# Camera-Interface.net
KiCad netlist of a schematic drawn in Altium Designer
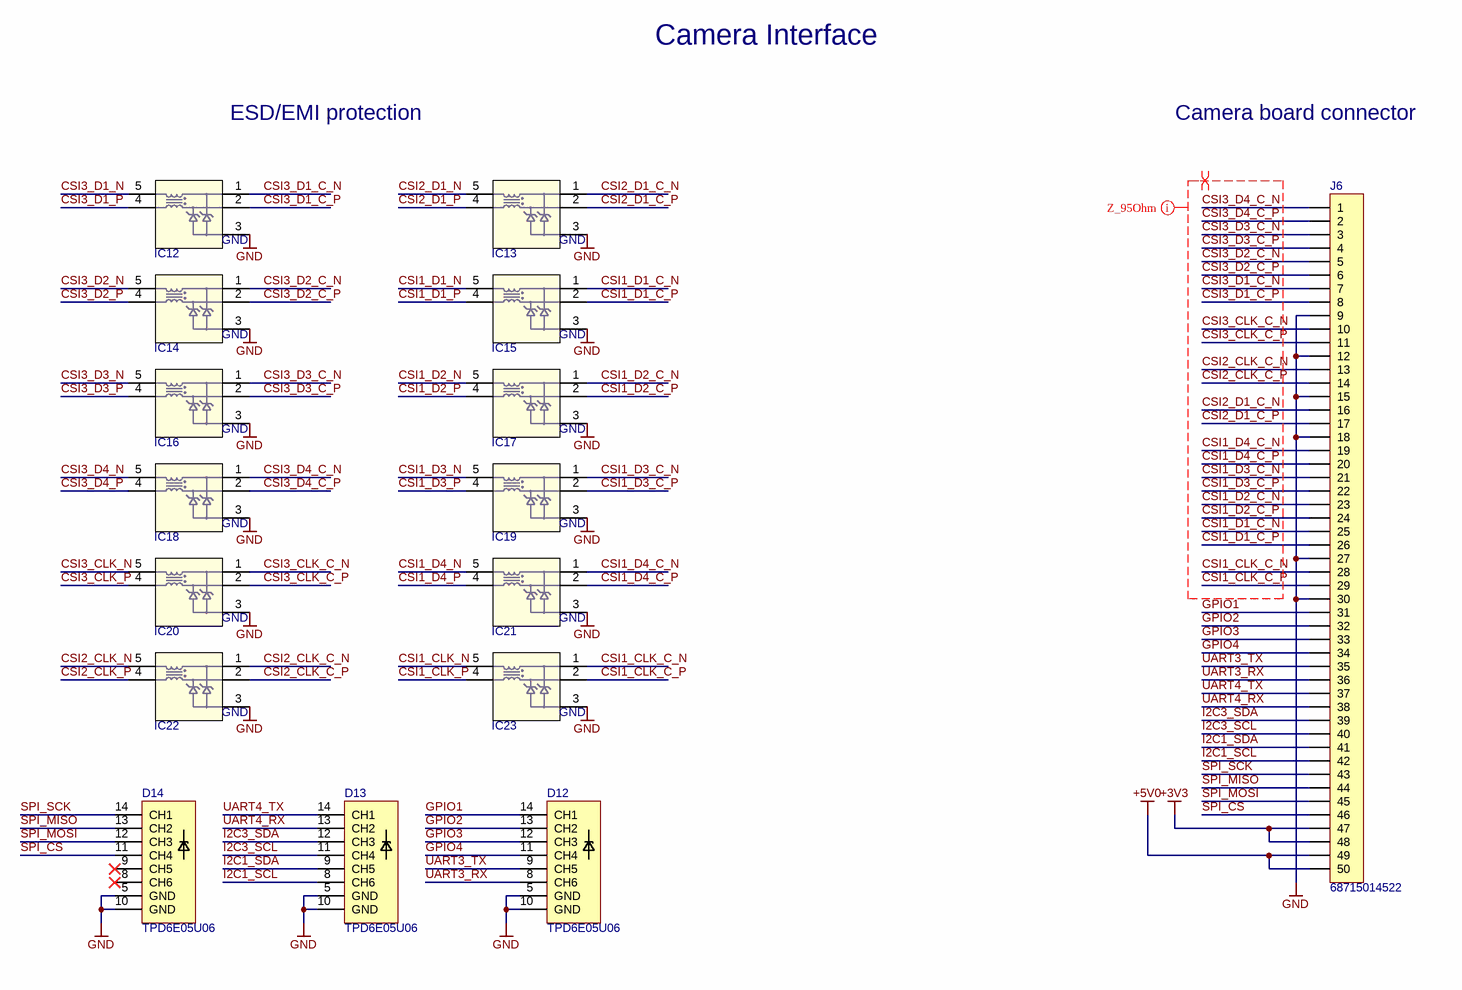
[diagram p0: Camera-Interface.SchDoc]

(export (version "E")
  (design (tool "Eeschema 10.0.6"))
  (components
    (comp (ref "D12")
      (value "TPD6E05U06")
      (footprint "TPD6E05U06_PASS")
      (description "ESD Suppressors 6-CH Pass through layout")
      (fields
        (field (name "PART NUMBER") "TPD6E05U06_PASS")
        (field (name "MANUFACTURER") "Texas Instruments")
      )
      (libsource (lib "TK1Baseboard") (part "TPD6E05U06_PASS"))
    )
    (comp (ref "D13")
      (value "TPD6E05U06")
      (footprint "TPD6E05U06_PASS")
      (description "ESD Suppressors 6-CH Pass through layout")
      (fields
        (field (name "PART NUMBER") "TPD6E05U06_PASS")
        (field (name "MANUFACTURER") "Texas Instruments")
      )
      (libsource (lib "TK1Baseboard") (part "TPD6E05U06_PASS"))
    )
    (comp (ref "D14")
      (value "TPD6E05U06")
      (footprint "TPD6E05U06_PASS")
      (description "ESD Suppressors 6-CH Pass through layout")
      (fields
        (field (name "PART NUMBER") "TPD6E05U06_PASS")
        (field (name "MANUFACTURER") "Texas Instruments")
      )
      (libsource (lib "TK1Baseboard") (part "TPD6E05U06_PASS"))
    )
    (comp (ref "IC12")
      (value "EClamp8052P")
      (footprint "SGP1917N5")
      (description "2-Line Common Mode Filter and Low Capacitance ESD Protection for MIPI USB")
      (fields (field (name "MANUFACTURER") "SEMTECH") (field (name "MPN") "ECLAMP8052P.TCT"))
      (libsource (lib "TK1Baseboard") (part "EClamp8052P"))
    )
    (comp (ref "IC13")
      (value "EClamp8052P")
      (footprint "SGP1917N5")
      (description "2-Line Common Mode Filter and Low Capacitance ESD Protection for MIPI USB")
      (fields (field (name "MANUFACTURER") "SEMTECH") (field (name "MPN") "ECLAMP8052P.TCT"))
      (libsource (lib "TK1Baseboard") (part "EClamp8052P"))
    )
    (comp (ref "IC14")
      (value "EClamp8052P")
      (footprint "SGP1917N5")
      (description "2-Line Common Mode Filter and Low Capacitance ESD Protection for MIPI USB")
      (fields (field (name "MANUFACTURER") "SEMTECH") (field (name "MPN") "ECLAMP8052P.TCT"))
      (libsource (lib "TK1Baseboard") (part "EClamp8052P"))
    )
    (comp (ref "IC15")
      (value "EClamp8052P")
      (footprint "SGP1917N5")
      (description "2-Line Common Mode Filter and Low Capacitance ESD Protection for MIPI USB")
      (fields (field (name "MANUFACTURER") "SEMTECH") (field (name "MPN") "ECLAMP8052P.TCT"))
      (libsource (lib "TK1Baseboard") (part "EClamp8052P"))
    )
    (comp (ref "IC16")
      (value "EClamp8052P")
      (footprint "SGP1917N5")
      (description "2-Line Common Mode Filter and Low Capacitance ESD Protection for MIPI USB")
      (fields (field (name "MANUFACTURER") "SEMTECH") (field (name "MPN") "ECLAMP8052P.TCT"))
      (libsource (lib "TK1Baseboard") (part "EClamp8052P"))
    )
    (comp (ref "IC17")
      (value "EClamp8052P")
      (footprint "SGP1917N5")
      (description "2-Line Common Mode Filter and Low Capacitance ESD Protection for MIPI USB")
      (fields (field (name "MANUFACTURER") "SEMTECH") (field (name "MPN") "ECLAMP8052P.TCT"))
      (libsource (lib "TK1Baseboard") (part "EClamp8052P"))
    )
    (comp (ref "IC18")
      (value "EClamp8052P")
      (footprint "SGP1917N5")
      (description "2-Line Common Mode Filter and Low Capacitance ESD Protection for MIPI USB")
      (fields (field (name "MANUFACTURER") "SEMTECH") (field (name "MPN") "ECLAMP8052P.TCT"))
      (libsource (lib "TK1Baseboard") (part "EClamp8052P"))
    )
    (comp (ref "IC19")
      (value "EClamp8052P")
      (footprint "SGP1917N5")
      (description "2-Line Common Mode Filter and Low Capacitance ESD Protection for MIPI USB")
      (fields (field (name "MANUFACTURER") "SEMTECH") (field (name "MPN") "ECLAMP8052P.TCT"))
      (libsource (lib "TK1Baseboard") (part "EClamp8052P"))
    )
    (comp (ref "IC20")
      (value "EClamp8052P")
      (footprint "SGP1917N5")
      (description "2-Line Common Mode Filter and Low Capacitance ESD Protection for MIPI USB")
      (fields (field (name "MANUFACTURER") "SEMTECH") (field (name "MPN") "ECLAMP8052P.TCT"))
      (libsource (lib "TK1Baseboard") (part "EClamp8052P"))
    )
    (comp (ref "IC21")
      (value "EClamp8052P")
      (footprint "SGP1917N5")
      (description "2-Line Common Mode Filter and Low Capacitance ESD Protection for MIPI USB")
      (fields (field (name "MANUFACTURER") "SEMTECH") (field (name "MPN") "ECLAMP8052P.TCT"))
      (libsource (lib "TK1Baseboard") (part "EClamp8052P"))
    )
    (comp (ref "IC22")
      (value "EClamp8052P")
      (footprint "SGP1917N5")
      (description "2-Line Common Mode Filter and Low Capacitance ESD Protection for MIPI USB")
      (fields (field (name "MANUFACTURER") "SEMTECH") (field (name "MPN") "ECLAMP8052P.TCT"))
      (libsource (lib "TK1Baseboard") (part "EClamp8052P"))
    )
    (comp (ref "IC23")
      (value "EClamp8052P")
      (footprint "SGP1917N5")
      (description "2-Line Common Mode Filter and Low Capacitance ESD Protection for MIPI USB")
      (fields (field (name "MANUFACTURER") "SEMTECH") (field (name "MPN") "ECLAMP8052P.TCT"))
      (libsource (lib "TK1Baseboard") (part "EClamp8052P"))
    )
    (comp (ref "J6")
      (value "68715014522")
      (footprint "68715014522")
      (description "0.50mm SMT ZIF Horizontal Bottom Contact WR-FPC")
      (fields
        (field (name "MANUFACTURER") "WURTH ELEKTRONIK")
        (field (name "PART NUMBER") "WE-687-150-145-22")
      )
      (libsource (lib "TK1Baseboard") (part "1X50"))
    )
  )
  (nets
    (net (code "1") (name "+3V3") (class "Default")
      (node (ref "J6") (pin "47") (pinfunction "47_47") (pintype "passive"))
      (node (ref "J6") (pin "48") (pinfunction "48_48") (pintype "passive"))
    )
    (net (code "2") (name "+5V0") (class "Default")
      (node (ref "J6") (pin "49") (pinfunction "49_49") (pintype "passive"))
      (node (ref "J6") (pin "50") (pinfunction "50_50") (pintype "passive"))
    )
    (net (code "3") (name "/CSI1_CLK_C_N") (class "Default")
      (node (ref "IC23") (pin "1") (pinfunction "1_1") (pintype "passive"))
      (node (ref "J6") (pin "28") (pinfunction "28_28") (pintype "passive"))
    )
    (net (code "4") (name "/CSI1_CLK_C_P") (class "Default")
      (node (ref "IC23") (pin "2") (pinfunction "2_2") (pintype "passive"))
      (node (ref "J6") (pin "29") (pinfunction "29_29") (pintype "passive"))
    )
    (net (code "5") (name "/CSI1_CLK_N") (class "Default")
      (node (ref "IC23") (pin "5") (pinfunction "5_5") (pintype "passive"))
    )
    (net (code "6") (name "/CSI1_CLK_P") (class "Default")
      (node (ref "IC23") (pin "4") (pinfunction "4_4") (pintype "passive"))
    )
    (net (code "7") (name "/CSI1_D1_C_N") (class "Default")
      (node (ref "IC15") (pin "1") (pinfunction "1_1") (pintype "passive"))
      (node (ref "J6") (pin "25") (pinfunction "25_25") (pintype "passive"))
    )
    (net (code "8") (name "/CSI1_D1_C_P") (class "Default")
      (node (ref "IC15") (pin "2") (pinfunction "2_2") (pintype "passive"))
      (node (ref "J6") (pin "26") (pinfunction "26_26") (pintype "passive"))
    )
    (net (code "9") (name "/CSI1_D1_N") (class "Default")
      (node (ref "IC15") (pin "5") (pinfunction "5_5") (pintype "passive"))
    )
    (net (code "10") (name "/CSI1_D1_P") (class "Default")
      (node (ref "IC15") (pin "4") (pinfunction "4_4") (pintype "passive"))
    )
    (net (code "11") (name "/CSI1_D2_C_N") (class "Default")
      (node (ref "IC17") (pin "1") (pinfunction "1_1") (pintype "passive"))
      (node (ref "J6") (pin "23") (pinfunction "23_23") (pintype "passive"))
    )
    (net (code "12") (name "/CSI1_D2_C_P") (class "Default")
      (node (ref "IC17") (pin "2") (pinfunction "2_2") (pintype "passive"))
      (node (ref "J6") (pin "24") (pinfunction "24_24") (pintype "passive"))
    )
    (net (code "13") (name "/CSI1_D2_N") (class "Default")
      (node (ref "IC17") (pin "5") (pinfunction "5_5") (pintype "passive"))
    )
    (net (code "14") (name "/CSI1_D2_P") (class "Default")
      (node (ref "IC17") (pin "4") (pinfunction "4_4") (pintype "passive"))
    )
    (net (code "15") (name "/CSI1_D3_C_N") (class "Default")
      (node (ref "IC19") (pin "1") (pinfunction "1_1") (pintype "passive"))
      (node (ref "J6") (pin "21") (pinfunction "21_21") (pintype "passive"))
    )
    (net (code "16") (name "/CSI1_D3_C_P") (class "Default")
      (node (ref "IC19") (pin "2") (pinfunction "2_2") (pintype "passive"))
      (node (ref "J6") (pin "22") (pinfunction "22_22") (pintype "passive"))
    )
    (net (code "17") (name "/CSI1_D3_N") (class "Default")
      (node (ref "IC19") (pin "5") (pinfunction "5_5") (pintype "passive"))
    )
    (net (code "18") (name "/CSI1_D3_P") (class "Default")
      (node (ref "IC19") (pin "4") (pinfunction "4_4") (pintype "passive"))
    )
    (net (code "19") (name "/CSI1_D4_C_N") (class "Default")
      (node (ref "IC21") (pin "1") (pinfunction "1_1") (pintype "passive"))
      (node (ref "J6") (pin "19") (pinfunction "19_19") (pintype "passive"))
    )
    (net (code "20") (name "/CSI1_D4_C_P") (class "Default")
      (node (ref "IC21") (pin "2") (pinfunction "2_2") (pintype "passive"))
      (node (ref "J6") (pin "20") (pinfunction "20_20") (pintype "passive"))
    )
    (net (code "21") (name "/CSI1_D4_N") (class "Default")
      (node (ref "IC21") (pin "5") (pinfunction "5_5") (pintype "passive"))
    )
    (net (code "22") (name "/CSI1_D4_P") (class "Default")
      (node (ref "IC21") (pin "4") (pinfunction "4_4") (pintype "passive"))
    )
    (net (code "23") (name "/CSI2_CLK_C_N") (class "Default")
      (node (ref "IC22") (pin "1") (pinfunction "1_1") (pintype "passive"))
      (node (ref "J6") (pin "13") (pinfunction "13_13") (pintype "passive"))
    )
    (net (code "24") (name "/CSI2_CLK_C_P") (class "Default")
      (node (ref "IC22") (pin "2") (pinfunction "2_2") (pintype "passive"))
      (node (ref "J6") (pin "14") (pinfunction "14_14") (pintype "passive"))
    )
    (net (code "25") (name "/CSI2_CLK_N") (class "Default")
      (node (ref "IC22") (pin "5") (pinfunction "5_5") (pintype "passive"))
    )
    (net (code "26") (name "/CSI2_CLK_P") (class "Default")
      (node (ref "IC22") (pin "4") (pinfunction "4_4") (pintype "passive"))
    )
    (net (code "27") (name "/CSI2_D1_C_N") (class "Default")
      (node (ref "IC13") (pin "1") (pinfunction "1_1") (pintype "passive"))
      (node (ref "J6") (pin "16") (pinfunction "16_16") (pintype "passive"))
    )
    (net (code "28") (name "/CSI2_D1_C_P") (class "Default")
      (node (ref "IC13") (pin "2") (pinfunction "2_2") (pintype "passive"))
      (node (ref "J6") (pin "17") (pinfunction "17_17") (pintype "passive"))
    )
    (net (code "29") (name "/CSI2_D1_N") (class "Default")
      (node (ref "IC13") (pin "5") (pinfunction "5_5") (pintype "passive"))
    )
    (net (code "30") (name "/CSI2_D1_P") (class "Default")
      (node (ref "IC13") (pin "4") (pinfunction "4_4") (pintype "passive"))
    )
    (net (code "31") (name "/CSI3_CLK_C_N") (class "Default")
      (node (ref "IC20") (pin "1") (pinfunction "1_1") (pintype "passive"))
      (node (ref "J6") (pin "10") (pinfunction "10_10") (pintype "passive"))
    )
    (net (code "32") (name "/CSI3_CLK_C_P") (class "Default")
      (node (ref "IC20") (pin "2") (pinfunction "2_2") (pintype "passive"))
      (node (ref "J6") (pin "11") (pinfunction "11_11") (pintype "passive"))
    )
    (net (code "33") (name "/CSI3_CLK_N") (class "Default")
      (node (ref "IC20") (pin "5") (pinfunction "5_5") (pintype "passive"))
    )
    (net (code "34") (name "/CSI3_CLK_P") (class "Default")
      (node (ref "IC20") (pin "4") (pinfunction "4_4") (pintype "passive"))
    )
    (net (code "35") (name "/CSI3_D1_C_N") (class "Default")
      (node (ref "IC12") (pin "1") (pinfunction "1_1") (pintype "passive"))
      (node (ref "J6") (pin "7") (pinfunction "7_7") (pintype "passive"))
    )
    (net (code "36") (name "/CSI3_D1_C_P") (class "Default")
      (node (ref "IC12") (pin "2") (pinfunction "2_2") (pintype "passive"))
      (node (ref "J6") (pin "8") (pinfunction "8_8") (pintype "passive"))
    )
    (net (code "37") (name "/CSI3_D1_N") (class "Default")
      (node (ref "IC12") (pin "5") (pinfunction "5_5") (pintype "passive"))
    )
    (net (code "38") (name "/CSI3_D1_P") (class "Default")
      (node (ref "IC12") (pin "4") (pinfunction "4_4") (pintype "passive"))
    )
    (net (code "39") (name "/CSI3_D2_C_N") (class "Default")
      (node (ref "IC14") (pin "1") (pinfunction "1_1") (pintype "passive"))
      (node (ref "J6") (pin "5") (pinfunction "5_5") (pintype "passive"))
    )
    (net (code "40") (name "/CSI3_D2_C_P") (class "Default")
      (node (ref "IC14") (pin "2") (pinfunction "2_2") (pintype "passive"))
      (node (ref "J6") (pin "6") (pinfunction "6_6") (pintype "passive"))
    )
    (net (code "41") (name "/CSI3_D2_N") (class "Default")
      (node (ref "IC14") (pin "5") (pinfunction "5_5") (pintype "passive"))
    )
    (net (code "42") (name "/CSI3_D2_P") (class "Default")
      (node (ref "IC14") (pin "4") (pinfunction "4_4") (pintype "passive"))
    )
    (net (code "43") (name "/CSI3_D3_C_N") (class "Default")
      (node (ref "IC16") (pin "1") (pinfunction "1_1") (pintype "passive"))
      (node (ref "J6") (pin "3") (pinfunction "3_3") (pintype "passive"))
    )
    (net (code "44") (name "/CSI3_D3_C_P") (class "Default")
      (node (ref "IC16") (pin "2") (pinfunction "2_2") (pintype "passive"))
      (node (ref "J6") (pin "4") (pinfunction "4_4") (pintype "passive"))
    )
    (net (code "45") (name "/CSI3_D3_N") (class "Default")
      (node (ref "IC16") (pin "5") (pinfunction "5_5") (pintype "passive"))
    )
    (net (code "46") (name "/CSI3_D3_P") (class "Default")
      (node (ref "IC16") (pin "4") (pinfunction "4_4") (pintype "passive"))
    )
    (net (code "47") (name "/CSI3_D4_C_N") (class "Default")
      (node (ref "IC18") (pin "1") (pinfunction "1_1") (pintype "passive"))
      (node (ref "J6") (pin "1") (pinfunction "1_1") (pintype "passive"))
    )
    (net (code "48") (name "/CSI3_D4_C_P") (class "Default")
      (node (ref "IC18") (pin "2") (pinfunction "2_2") (pintype "passive"))
      (node (ref "J6") (pin "2") (pinfunction "2_2") (pintype "passive"))
    )
    (net (code "49") (name "/CSI3_D4_N") (class "Default")
      (node (ref "IC18") (pin "5") (pinfunction "5_5") (pintype "passive"))
    )
    (net (code "50") (name "/CSI3_D4_P") (class "Default")
      (node (ref "IC18") (pin "4") (pinfunction "4_4") (pintype "passive"))
    )
    (net (code "51") (name "/GPIO1") (class "Default")
      (node (ref "D12") (pin "14") (pinfunction "CH1_14") (pintype "passive"))
      (node (ref "J6") (pin "31") (pinfunction "31_31") (pintype "passive"))
    )
    (net (code "52") (name "/GPIO2") (class "Default")
      (node (ref "D12") (pin "13") (pinfunction "CH2_13") (pintype "passive"))
      (node (ref "J6") (pin "32") (pinfunction "32_32") (pintype "passive"))
    )
    (net (code "53") (name "/GPIO3") (class "Default")
      (node (ref "D12") (pin "12") (pinfunction "CH3_12") (pintype "passive"))
      (node (ref "J6") (pin "33") (pinfunction "33_33") (pintype "passive"))
    )
    (net (code "54") (name "/GPIO4") (class "Default")
      (node (ref "D12") (pin "11") (pinfunction "CH4_11") (pintype "passive"))
      (node (ref "J6") (pin "34") (pinfunction "34_34") (pintype "passive"))
    )
    (net (code "55") (name "/I2C1_SCL") (class "Default")
      (node (ref "D13") (pin "8") (pinfunction "CH6_8") (pintype "passive"))
      (node (ref "J6") (pin "42") (pinfunction "42_42") (pintype "passive"))
    )
    (net (code "56") (name "/I2C1_SDA") (class "Default")
      (node (ref "D13") (pin "9") (pinfunction "CH5_9") (pintype "passive"))
      (node (ref "J6") (pin "41") (pinfunction "41_41") (pintype "passive"))
    )
    (net (code "57") (name "/I2C3_SCL") (class "Default")
      (node (ref "D13") (pin "11") (pinfunction "CH4_11") (pintype "passive"))
      (node (ref "J6") (pin "40") (pinfunction "40_40") (pintype "passive"))
    )
    (net (code "58") (name "/I2C3_SDA") (class "Default")
      (node (ref "D13") (pin "12") (pinfunction "CH3_12") (pintype "passive"))
      (node (ref "J6") (pin "39") (pinfunction "39_39") (pintype "passive"))
    )
    (net (code "59") (name "/SPI_CS") (class "Default")
      (node (ref "D14") (pin "11") (pinfunction "CH4_11") (pintype "passive"))
      (node (ref "J6") (pin "46") (pinfunction "46_46") (pintype "passive"))
    )
    (net (code "60") (name "/SPI_MISO") (class "Default")
      (node (ref "D14") (pin "13") (pinfunction "CH2_13") (pintype "passive"))
      (node (ref "J6") (pin "44") (pinfunction "44_44") (pintype "passive"))
    )
    (net (code "61") (name "/SPI_MOSI") (class "Default")
      (node (ref "D14") (pin "12") (pinfunction "CH3_12") (pintype "passive"))
      (node (ref "J6") (pin "45") (pinfunction "45_45") (pintype "passive"))
    )
    (net (code "62") (name "/SPI_SCK") (class "Default")
      (node (ref "D14") (pin "14") (pinfunction "CH1_14") (pintype "passive"))
      (node (ref "J6") (pin "43") (pinfunction "43_43") (pintype "passive"))
    )
    (net (code "63") (name "/UART3_RX") (class "Default")
      (node (ref "D12") (pin "8") (pinfunction "CH6_8") (pintype "passive"))
      (node (ref "J6") (pin "36") (pinfunction "36_36") (pintype "passive"))
    )
    (net (code "64") (name "/UART3_TX") (class "Default")
      (node (ref "D12") (pin "9") (pinfunction "CH5_9") (pintype "passive"))
      (node (ref "J6") (pin "35") (pinfunction "35_35") (pintype "passive"))
    )
    (net (code "65") (name "/UART4_RX") (class "Default")
      (node (ref "D13") (pin "13") (pinfunction "CH2_13") (pintype "passive"))
      (node (ref "J6") (pin "38") (pinfunction "38_38") (pintype "passive"))
    )
    (net (code "66") (name "/UART4_TX") (class "Default")
      (node (ref "D13") (pin "14") (pinfunction "CH1_14") (pintype "passive"))
      (node (ref "J6") (pin "37") (pinfunction "37_37") (pintype "passive"))
    )
    (net (code "67") (name "GND") (class "Default")
      (node (ref "D12") (pin "10") (pinfunction "GND_10") (pintype "passive"))
      (node (ref "D12") (pin "5") (pinfunction "GND_5") (pintype "passive"))
      (node (ref "D13") (pin "10") (pinfunction "GND_10") (pintype "passive"))
      (node (ref "D13") (pin "5") (pinfunction "GND_5") (pintype "passive"))
      (node (ref "D14") (pin "10") (pinfunction "GND_10") (pintype "passive"))
      (node (ref "D14") (pin "5") (pinfunction "GND_5") (pintype "passive"))
      (node (ref "IC12") (pin "3") (pinfunction "GND_3") (pintype "passive"))
      (node (ref "IC13") (pin "3") (pinfunction "GND_3") (pintype "passive"))
      (node (ref "IC14") (pin "3") (pinfunction "GND_3") (pintype "passive"))
      (node (ref "IC15") (pin "3") (pinfunction "GND_3") (pintype "passive"))
      (node (ref "IC16") (pin "3") (pinfunction "GND_3") (pintype "passive"))
      (node (ref "IC17") (pin "3") (pinfunction "GND_3") (pintype "passive"))
      (node (ref "IC18") (pin "3") (pinfunction "GND_3") (pintype "passive"))
      (node (ref "IC19") (pin "3") (pinfunction "GND_3") (pintype "passive"))
      (node (ref "IC20") (pin "3") (pinfunction "GND_3") (pintype "passive"))
      (node (ref "IC21") (pin "3") (pinfunction "GND_3") (pintype "passive"))
      (node (ref "IC22") (pin "3") (pinfunction "GND_3") (pintype "passive"))
      (node (ref "IC23") (pin "3") (pinfunction "GND_3") (pintype "passive"))
      (node (ref "J6") (pin "12") (pinfunction "12_12") (pintype "passive"))
      (node (ref "J6") (pin "15") (pinfunction "15_15") (pintype "passive"))
      (node (ref "J6") (pin "18") (pinfunction "18_18") (pintype "passive"))
      (node (ref "J6") (pin "27") (pinfunction "27_27") (pintype "passive"))
      (node (ref "J6") (pin "30") (pinfunction "30_30") (pintype "passive"))
      (node (ref "J6") (pin "9") (pinfunction "9_9") (pintype "passive"))
    )
    (net (code "68") (name "unconnected-(D14-CH5-Pad9)") (class "Default")
      (node (ref "D14") (pin "9") (pinfunction "CH5_9") (pintype "passive+no_connect"))
    )
    (net (code "69") (name "unconnected-(D14-CH6-Pad8)") (class "Default")
      (node (ref "D14") (pin "8") (pinfunction "CH6_8") (pintype "passive+no_connect"))
    )
  )
)
